# traintrackr_schematic.net
KiCad netlist of a schematic drawn in Altium Designer
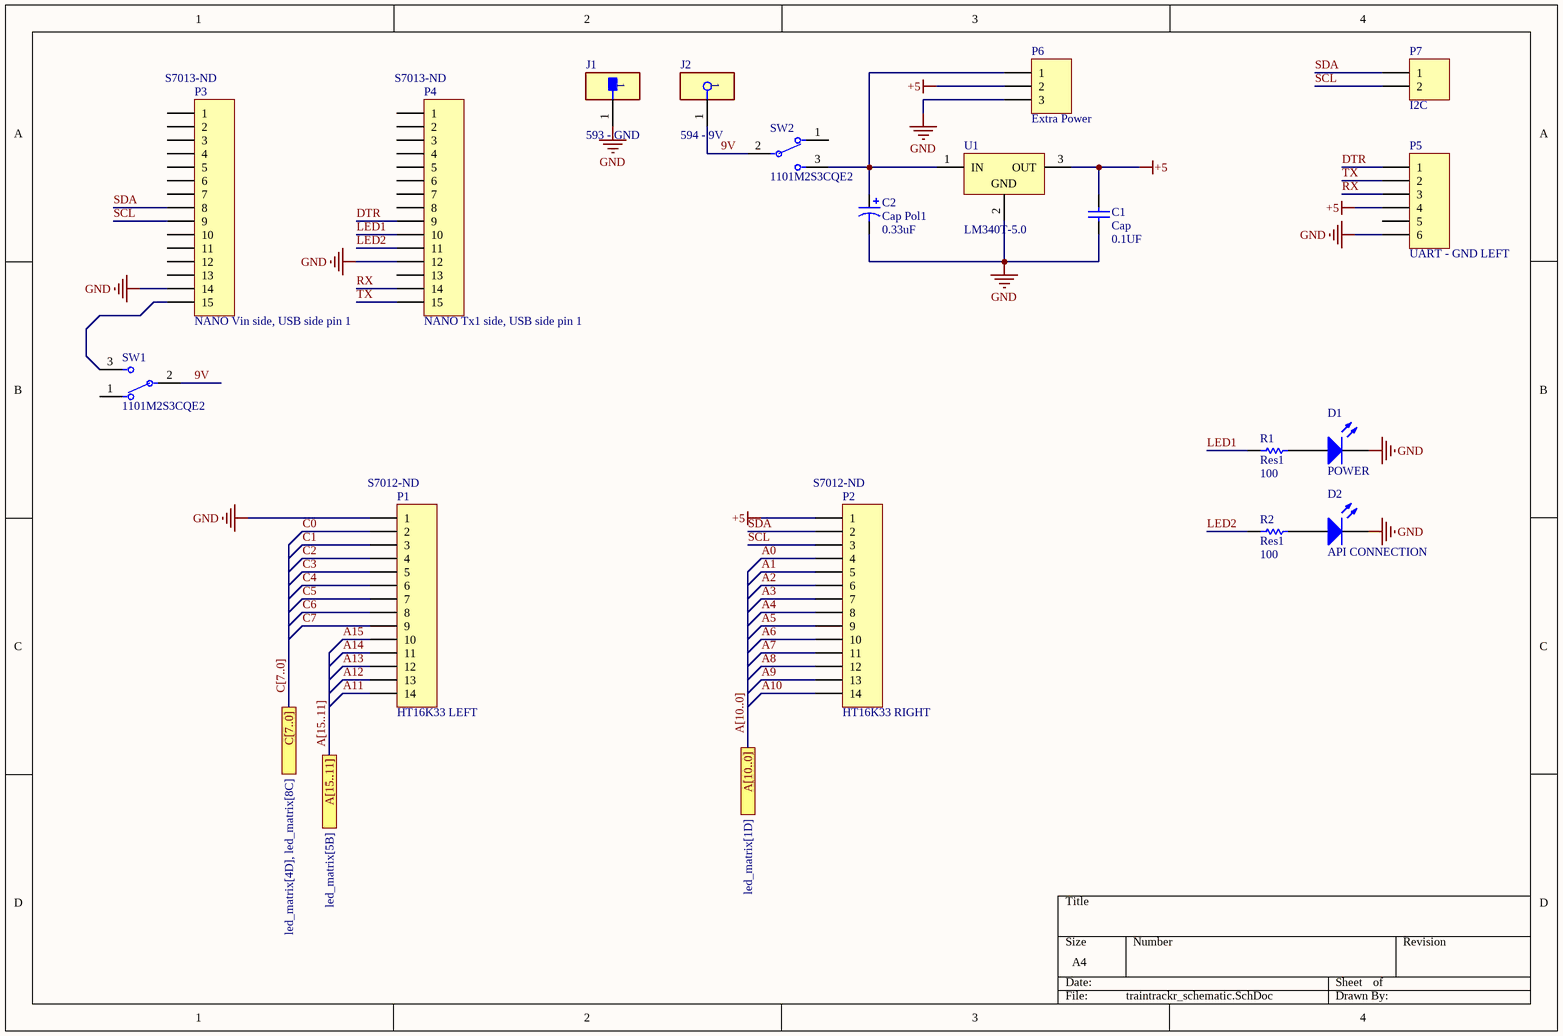
[diagram p0: traintrackr_schematic.SchDoc]

(export (version "E")
  (design (tool "Eeschema 10.0.6"))
  (components
    (comp (ref "C1")
      (value "Cap")
      (footprint "RAD-0.1")
      (description "Capacitor")
      (fields
        (field (name "ALTIUM_VALUE") "0.1UF")
        (field (name "MANUFACTURER PART NUMBER") "K104M15X7RF5TH5")
        (field (name "PUBLISHER") "Altium Limited")
      )
      (libsource (lib "ECE295-Capacitors-TH") (part "CAP CER 0.1UF 50V X7R RADIAL"))
    )
    (comp (ref "C2")
      (value "Cap Pol1")
      (footprint "Capacitor 330nF")
      (description "Polarized Capacitor (Radial)")
      (fields (field (name "ALTIUM_VALUE") "0.33uF") (field (name "PUBLISHER") "Altium Limited"))
      (libsource (lib "Miscellaneous Devices") (part "Cap Pol1"))
    )
    (comp (ref "D1")
      (value "POWER")
      (footprint "LED_5MM")
      (description "Typical RED GaAs LED")
      (fields (field (name "PUBLISHER") "Altium Limited"))
      (libsource (lib "Miscellaneous Devices") (part "LED1"))
    )
    (comp (ref "D2")
      (value "API CONNECTION")
      (footprint "LED_5MM")
      (description "Typical RED GaAs LED")
      (fields (field (name "PUBLISHER") "Altium Limited"))
      (libsource (lib "Miscellaneous Devices") (part "LED1"))
    )
    (comp (ref "J1")
      (value "593 - GND")
      (footprint "FP-593-MFG")
      (description "BATTERY CONTACT SNAP 9V PC PIN")
      (libsource (lib "Altium Content Vault") (part "dd45045ce8184df9e99e12baf3f412c"))
    )
    (comp (ref "J2")
      (value "594 - 9V")
      (footprint "FP-594-MFG")
      (description "BATTERY CONTACT SNAP 9V PC PIN")
      (libsource (lib "Altium Content Vault") (part "c5c826e0c4b67fe3b42ef77f2d4decc"))
    )
    (comp (ref "P1")
      (value "HT16K33 LEFT")
      (footprint "HDR1X14")
      (description "Header, 14-Pin")
      (fields (field (name "SUPPLIER PART NUMBER 1") "S7012-ND") (field (name "PUBLISHER") "Altium Limited"))
      (libsource (lib "Miscellaneous Connectors") (part "Header 14"))
    )
    (comp (ref "P2")
      (value "HT16K33 RIGHT")
      (footprint "HDR1X14")
      (description "Header, 14-Pin")
      (fields (field (name "SUPPLIER PART NUMBER 1") "S7012-ND") (field (name "PUBLISHER") "Altium Limited"))
      (libsource (lib "Miscellaneous Connectors") (part "Header 14"))
    )
    (comp (ref "P3")
      (value "NANO Vin side, USB side pin 1")
      (footprint "HDR1X15")
      (description "Header, 15-Pin")
      (fields (field (name "SUPPLIER PART NUMBER 1") "S7013-ND") (field (name "PUBLISHER") "Altium Limited"))
      (libsource (lib "Miscellaneous Connectors") (part "Header 15"))
    )
    (comp (ref "P4")
      (value "NANO Tx1 side, USB side pin 1")
      (footprint "HDR1X15")
      (description "Header, 15-Pin")
      (fields (field (name "SUPPLIER PART NUMBER 1") "S7013-ND") (field (name "PUBLISHER") "Altium Limited"))
      (libsource (lib "Miscellaneous Connectors") (part "Header 15"))
    )
    (comp (ref "P5")
      (value "UART - GND LEFT")
      (footprint "HDR1X6H")
      (description "Header, 6-Pin, Right Angle")
      (fields (field (name "PUBLISHER") "Altium Limited"))
      (libsource (lib "Miscellaneous Connectors") (part "Header 6H"))
    )
    (comp (ref "P6")
      (value "Extra Power")
      (footprint "HDR1X3")
      (description "Header, 3-Pin")
      (fields (field (name "PUBLISHER") "Altium Limited"))
      (libsource (lib "Miscellaneous Connectors") (part "Header 3"))
    )
    (comp (ref "P7")
      (value "I2C")
      (footprint "RAD-0.1")
      (description "Header, 2-Pin, Right Angle")
      (fields (field (name "PUBLISHER") "Altium Limited"))
      (libsource (lib "Miscellaneous Connectors") (part "Header 2H"))
    )
    (comp (ref "R1")
      (value "Res1")
      (footprint "AXIAL-0.3")
      (description "Resistor")
      (fields (field (name "ALTIUM_VALUE") "100") (field (name "PUBLISHER") "Altium Limited"))
      (libsource (lib "Miscellaneous Devices") (part "Res1"))
    )
    (comp (ref "R2")
      (value "Res1")
      (footprint "AXIAL-0.3")
      (description "Resistor")
      (fields (field (name "ALTIUM_VALUE") "100") (field (name "PUBLISHER") "Altium Limited"))
      (libsource (lib "Miscellaneous Devices") (part "Res1"))
    )
    (comp (ref "SW1")
      (value "1101M2S3CQE2")
      (footprint "FP-1101M2S3CQE2-MFG")
      (description "SWITCH SLIDE SPDT 6A 120V")
      (libsource (lib "Altium Content Vault") (part "7fcaa069a19c2acd609832313418d7c"))
    )
    (comp (ref "SW2")
      (value "1101M2S3CQE2")
      (footprint "FP-1101M2S3CQE2-MFG")
      (description "SWITCH SLIDE SPDT 6A 120V")
      (libsource (lib "Altium Content Vault") (part "7fcaa069a19c2acd609832313418d7c"))
    )
    (comp (ref "U1")
      (value "LM340T-5.0")
      (footprint "NDE0003A")
      (description "Series 3-Terminal Positive Regulators, 3-pin TO-220")
      (fields (field (name "MANUFACTURER") "Texas Instruments"))
      (libsource (lib "Altium Content Vault") (part "PM-REG-LM2940-SIL3"))
    )
  )
  (nets
    (net (code "1") (name "+5") (class "Default")
      (node (ref "C1") (pin "2") (pinfunction "2_2") (pintype "passive"))
      (node (ref "P2") (pin "1") (pinfunction "1_1") (pintype "passive"))
      (node (ref "P5") (pin "4") (pinfunction "4_4") (pintype "passive"))
      (node (ref "P6") (pin "2") (pinfunction "2_2") (pintype "passive"))
      (node (ref "U1") (pin "3") (pinfunction "OUT_3") (pintype "power_in"))
    )
    (net (code "2") (name "/9V") (class "Default")
      (node (ref "J2") (pin "1") (pinfunction "1_1") (pintype "passive"))
      (node (ref "SW1") (pin "2") (pinfunction "COMM_2") (pintype "passive"))
      (node (ref "SW2") (pin "2") (pinfunction "COMM_2") (pintype "passive"))
    )
    (net (code "3") (name "/A0") (class "Default")
      (node (ref "P2") (pin "4") (pinfunction "4_4") (pintype "passive"))
    )
    (net (code "4") (name "/A1") (class "Default")
      (node (ref "P2") (pin "5") (pinfunction "5_5") (pintype "passive"))
    )
    (net (code "5") (name "/A2") (class "Default")
      (node (ref "P2") (pin "6") (pinfunction "6_6") (pintype "passive"))
    )
    (net (code "6") (name "/A3") (class "Default")
      (node (ref "P2") (pin "7") (pinfunction "7_7") (pintype "passive"))
    )
    (net (code "7") (name "/A4") (class "Default")
      (node (ref "P2") (pin "8") (pinfunction "8_8") (pintype "passive"))
    )
    (net (code "8") (name "/A5") (class "Default")
      (node (ref "P2") (pin "9") (pinfunction "9_9") (pintype "passive"))
    )
    (net (code "9") (name "/A6") (class "Default")
      (node (ref "P2") (pin "10") (pinfunction "10_10") (pintype "passive"))
    )
    (net (code "10") (name "/A7") (class "Default")
      (node (ref "P2") (pin "11") (pinfunction "11_11") (pintype "passive"))
    )
    (net (code "11") (name "/A8") (class "Default")
      (node (ref "P2") (pin "12") (pinfunction "12_12") (pintype "passive"))
    )
    (net (code "12") (name "/A9") (class "Default")
      (node (ref "P2") (pin "13") (pinfunction "13_13") (pintype "passive"))
    )
    (net (code "13") (name "/A10") (class "Default")
      (node (ref "P2") (pin "14") (pinfunction "14_14") (pintype "passive"))
    )
    (net (code "14") (name "/A11") (class "Default")
      (node (ref "P1") (pin "14") (pinfunction "14_14") (pintype "passive"))
    )
    (net (code "15") (name "/A12") (class "Default")
      (node (ref "P1") (pin "13") (pinfunction "13_13") (pintype "passive"))
    )
    (net (code "16") (name "/A13") (class "Default")
      (node (ref "P1") (pin "12") (pinfunction "12_12") (pintype "passive"))
    )
    (net (code "17") (name "/A14") (class "Default")
      (node (ref "P1") (pin "11") (pinfunction "11_11") (pintype "passive"))
    )
    (net (code "18") (name "/A15") (class "Default")
      (node (ref "P1") (pin "10") (pinfunction "10_10") (pintype "passive"))
    )
    (net (code "21") (name "/C0") (class "Default")
      (node (ref "P1") (pin "2") (pinfunction "2_2") (pintype "passive"))
    )
    (net (code "22") (name "/C1") (class "Default")
      (node (ref "P1") (pin "3") (pinfunction "3_3") (pintype "passive"))
    )
    (net (code "23") (name "/C2") (class "Default")
      (node (ref "P1") (pin "4") (pinfunction "4_4") (pintype "passive"))
    )
    (net (code "24") (name "/C3") (class "Default")
      (node (ref "P1") (pin "5") (pinfunction "5_5") (pintype "passive"))
    )
    (net (code "25") (name "/C4") (class "Default")
      (node (ref "P1") (pin "6") (pinfunction "6_6") (pintype "passive"))
    )
    (net (code "26") (name "/C5") (class "Default")
      (node (ref "P1") (pin "7") (pinfunction "7_7") (pintype "passive"))
    )
    (net (code "27") (name "/C6") (class "Default")
      (node (ref "P1") (pin "8") (pinfunction "8_8") (pintype "passive"))
    )
    (net (code "28") (name "/C7") (class "Default")
      (node (ref "P1") (pin "9") (pinfunction "9_9") (pintype "passive"))
    )
    (net (code "30") (name "/DTR") (class "Default")
      (node (ref "P4") (pin "9") (pinfunction "9_9") (pintype "passive"))
      (node (ref "P5") (pin "1") (pinfunction "1_1") (pintype "passive"))
    )
    (net (code "31") (name "/LED1") (class "Default")
      (node (ref "P4") (pin "10") (pinfunction "10_10") (pintype "passive"))
      (node (ref "R1") (pin "1") (pinfunction "1_1") (pintype "passive"))
    )
    (net (code "32") (name "/LED2") (class "Default")
      (node (ref "P4") (pin "11") (pinfunction "11_11") (pintype "passive"))
      (node (ref "R2") (pin "1") (pinfunction "1_1") (pintype "passive"))
    )
    (net (code "33") (name "/RX") (class "Default")
      (node (ref "P4") (pin "14") (pinfunction "14_14") (pintype "passive"))
      (node (ref "P5") (pin "3") (pinfunction "3_3") (pintype "passive"))
    )
    (net (code "34") (name "/SCL") (class "Default")
      (node (ref "P2") (pin "3") (pinfunction "3_3") (pintype "passive"))
      (node (ref "P3") (pin "9") (pinfunction "9_9") (pintype "passive"))
      (node (ref "P7") (pin "2") (pinfunction "2_2") (pintype "passive"))
    )
    (net (code "35") (name "/SDA") (class "Default")
      (node (ref "P2") (pin "2") (pinfunction "2_2") (pintype "passive"))
      (node (ref "P3") (pin "8") (pinfunction "8_8") (pintype "passive"))
      (node (ref "P7") (pin "1") (pinfunction "1_1") (pintype "passive"))
    )
    (net (code "36") (name "/TX") (class "Default")
      (node (ref "P4") (pin "15") (pinfunction "15_15") (pintype "passive"))
      (node (ref "P5") (pin "2") (pinfunction "2_2") (pintype "passive"))
    )
    (net (code "37") (name "GND") (class "Default")
      (node (ref "C1") (pin "1") (pinfunction "1_1") (pintype "passive"))
      (node (ref "C2") (pin "2") (pinfunction "2_2") (pintype "passive"))
      (node (ref "D1") (pin "2") (pinfunction "K_2") (pintype "passive"))
      (node (ref "D2") (pin "2") (pinfunction "K_2") (pintype "passive"))
      (node (ref "J1") (pin "1") (pinfunction "1_1") (pintype "passive"))
      (node (ref "P1") (pin "1") (pinfunction "1_1") (pintype "passive"))
      (node (ref "P3") (pin "14") (pinfunction "14_14") (pintype "passive"))
      (node (ref "P4") (pin "12") (pinfunction "12_12") (pintype "passive"))
      (node (ref "P5") (pin "6") (pinfunction "6_6") (pintype "passive"))
      (node (ref "P6") (pin "3") (pinfunction "3_3") (pintype "passive"))
      (node (ref "U1") (pin "2") (pinfunction "GND_2") (pintype "power_in"))
    )
    (net (code "38") (name "Net-(D1-A)") (class "Default")
      (node (ref "D1") (pin "1") (pinfunction "A_1") (pintype "passive"))
      (node (ref "R1") (pin "2") (pinfunction "2_2") (pintype "passive"))
    )
    (net (code "39") (name "Net-(D2-A)") (class "Default")
      (node (ref "D2") (pin "1") (pinfunction "A_1") (pintype "passive"))
      (node (ref "R2") (pin "2") (pinfunction "2_2") (pintype "passive"))
    )
    (net (code "40") (name "Net-(P3-Pad15)") (class "Default")
      (node (ref "P3") (pin "15") (pinfunction "15_15") (pintype "passive"))
      (node (ref "SW1") (pin "3") (pinfunction "3_3") (pintype "passive"))
    )
    (net (code "41") (name "Net-(U1-IN)") (class "Default")
      (node (ref "C2") (pin "1") (pinfunction "1_1") (pintype "passive"))
      (node (ref "P6") (pin "1") (pinfunction "1_1") (pintype "passive"))
      (node (ref "SW2") (pin "3") (pinfunction "3_3") (pintype "passive"))
      (node (ref "U1") (pin "1") (pinfunction "IN_1") (pintype "power_in"))
    )
    (net (code "42") (name "unconnected-(P3-Pad1)") (class "Default")
      (node (ref "P3") (pin "1") (pinfunction "1_1") (pintype "passive"))
    )
    (net (code "43") (name "unconnected-(P3-Pad2)") (class "Default")
      (node (ref "P3") (pin "2") (pinfunction "2_2") (pintype "passive"))
    )
    (net (code "44") (name "unconnected-(P3-Pad3)") (class "Default")
      (node (ref "P3") (pin "3") (pinfunction "3_3") (pintype "passive"))
    )
    (net (code "45") (name "unconnected-(P3-Pad4)") (class "Default")
      (node (ref "P3") (pin "4") (pinfunction "4_4") (pintype "passive"))
    )
    (net (code "46") (name "unconnected-(P3-Pad5)") (class "Default")
      (node (ref "P3") (pin "5") (pinfunction "5_5") (pintype "passive"))
    )
    (net (code "47") (name "unconnected-(P3-Pad6)") (class "Default")
      (node (ref "P3") (pin "6") (pinfunction "6_6") (pintype "passive"))
    )
    (net (code "48") (name "unconnected-(P3-Pad7)") (class "Default")
      (node (ref "P3") (pin "7") (pinfunction "7_7") (pintype "passive"))
    )
    (net (code "49") (name "unconnected-(P3-Pad10)") (class "Default")
      (node (ref "P3") (pin "10") (pinfunction "10_10") (pintype "passive"))
    )
    (net (code "50") (name "unconnected-(P3-Pad11)") (class "Default")
      (node (ref "P3") (pin "11") (pinfunction "11_11") (pintype "passive"))
    )
    (net (code "51") (name "unconnected-(P3-Pad12)") (class "Default")
      (node (ref "P3") (pin "12") (pinfunction "12_12") (pintype "passive"))
    )
    (net (code "52") (name "unconnected-(P3-Pad13)") (class "Default")
      (node (ref "P3") (pin "13") (pinfunction "13_13") (pintype "passive"))
    )
    (net (code "53") (name "unconnected-(P4-Pad1)") (class "Default")
      (node (ref "P4") (pin "1") (pinfunction "1_1") (pintype "passive"))
    )
    (net (code "54") (name "unconnected-(P4-Pad2)") (class "Default")
      (node (ref "P4") (pin "2") (pinfunction "2_2") (pintype "passive"))
    )
    (net (code "55") (name "unconnected-(P4-Pad3)") (class "Default")
      (node (ref "P4") (pin "3") (pinfunction "3_3") (pintype "passive"))
    )
    (net (code "56") (name "unconnected-(P4-Pad4)") (class "Default")
      (node (ref "P4") (pin "4") (pinfunction "4_4") (pintype "passive"))
    )
    (net (code "57") (name "unconnected-(P4-Pad5)") (class "Default")
      (node (ref "P4") (pin "5") (pinfunction "5_5") (pintype "passive"))
    )
    (net (code "58") (name "unconnected-(P4-Pad6)") (class "Default")
      (node (ref "P4") (pin "6") (pinfunction "6_6") (pintype "passive"))
    )
    (net (code "59") (name "unconnected-(P4-Pad7)") (class "Default")
      (node (ref "P4") (pin "7") (pinfunction "7_7") (pintype "passive"))
    )
    (net (code "60") (name "unconnected-(P4-Pad8)") (class "Default")
      (node (ref "P4") (pin "8") (pinfunction "8_8") (pintype "passive"))
    )
    (net (code "61") (name "unconnected-(P4-Pad13)") (class "Default")
      (node (ref "P4") (pin "13") (pinfunction "13_13") (pintype "passive"))
    )
    (net (code "62") (name "unconnected-(P5-Pad5)") (class "Default")
      (node (ref "P5") (pin "5") (pinfunction "5_5") (pintype "passive"))
    )
    (net (code "63") (name "unconnected-(SW1-Pad1)") (class "Default")
      (node (ref "SW1") (pin "1") (pinfunction "1_1") (pintype "passive"))
    )
    (net (code "64") (name "unconnected-(SW2-Pad1)") (class "Default")
      (node (ref "SW2") (pin "1") (pinfunction "1_1") (pintype "passive"))
    )
  )
)
